# IOPower.net
KiCad netlist of a schematic drawn in Altium Designer
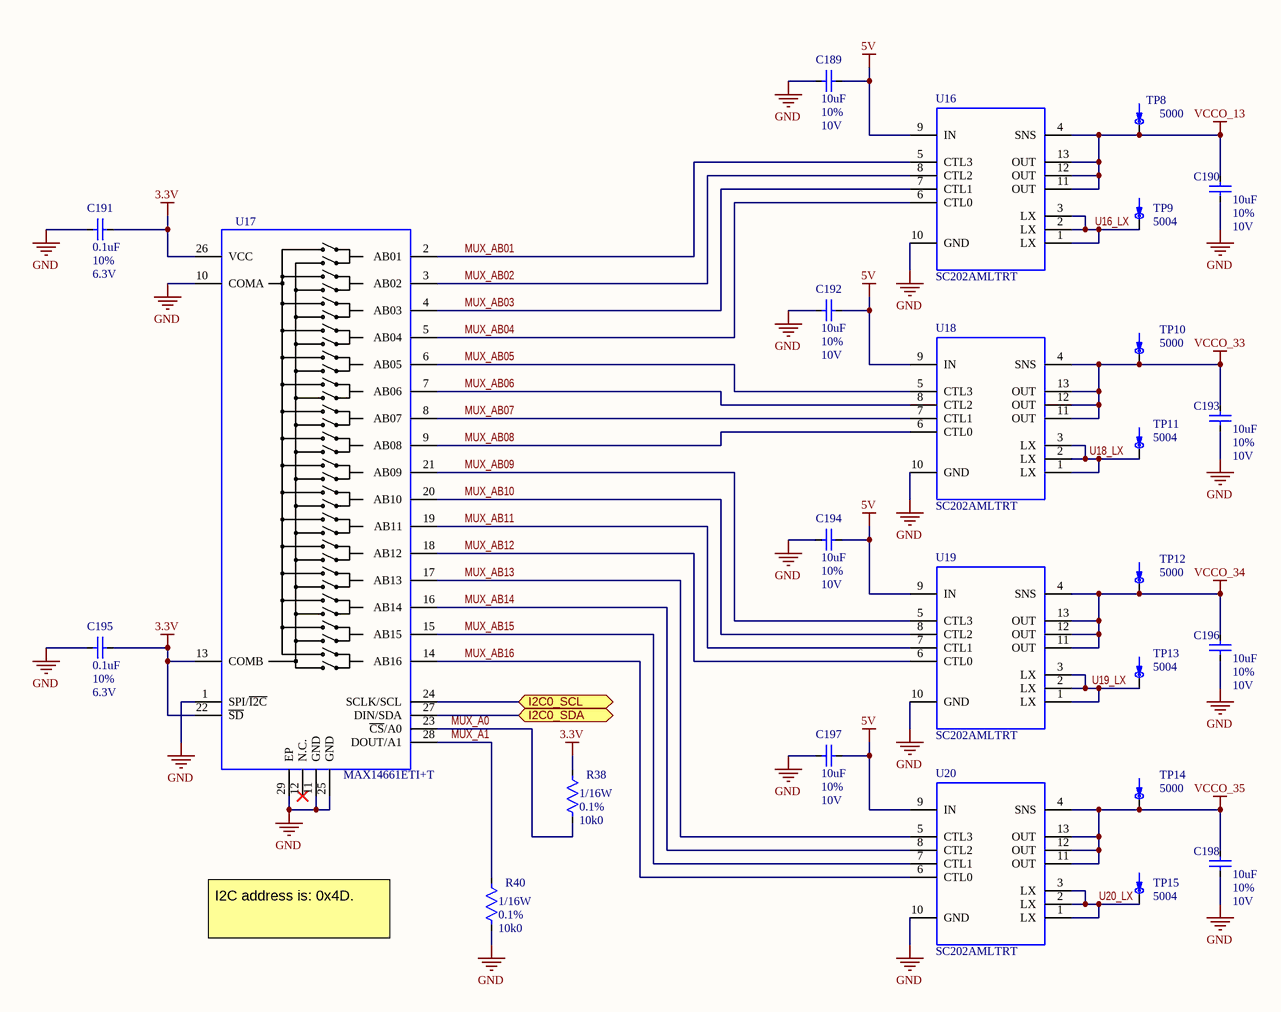
[diagram p0: IOPower.SchDoc]

(export (version "E")
  (design (tool "Eeschema 10.0.6"))
  (components
    (comp (ref "C189")
      (value "10uF")
      (footprint "CAPC1608X38N")
      (description "Capacitor ceramic, X5R, 10uF, 10V, 10%, -55 to +85 C, EIA0603")
      (fields
        (field (name "TOLERANCE") "10%")
        (field (name "VOLTAGE") "10V")
        (field (name "Comment") "CAPACITOR_NP_TYPE1")
      )
      (libsource (lib "parts") (part "CAPACITOR_NP_TYPE1"))
    )
    (comp (ref "C190")
      (value "10uF")
      (footprint "CAPC1608X38N")
      (description "Capacitor ceramic, X5R, 10uF, 10V, 10%, -55 to +85 C, EIA0603")
      (fields
        (field (name "TOLERANCE") "10%")
        (field (name "VOLTAGE") "10V")
        (field (name "Comment") "CAPACITOR_NP_TYPE1")
      )
      (libsource (lib "parts") (part "CAPACITOR_NP_TYPE1"))
    )
    (comp (ref "C191")
      (value "0.1uF")
      (footprint "CAPC0603X33N")
      (description "Capacitor ceramic, X5R, 0.1uF, 6.3V, 10%, -55 to +125 C, EIA0201")
      (fields
        (field (name "TOLERANCE") "10%")
        (field (name "VOLTAGE") "6.3V")
        (field (name "Comment") "CAPACITOR_NP_TYPE1")
      )
      (libsource (lib "parts") (part "CAPACITOR_NP_TYPE1"))
    )
    (comp (ref "C192")
      (value "10uF")
      (footprint "CAPC1608X38N")
      (description "Capacitor ceramic, X5R, 10uF, 10V, 10%, -55 to +85 C, EIA0603")
      (fields
        (field (name "TOLERANCE") "10%")
        (field (name "VOLTAGE") "10V")
        (field (name "Comment") "CAPACITOR_NP_TYPE1")
      )
      (libsource (lib "parts") (part "CAPACITOR_NP_TYPE1"))
    )
    (comp (ref "C193")
      (value "10uF")
      (footprint "CAPC1608X38N")
      (description "Capacitor ceramic, X5R, 10uF, 10V, 10%, -55 to +85 C, EIA0603")
      (fields
        (field (name "TOLERANCE") "10%")
        (field (name "VOLTAGE") "10V")
        (field (name "Comment") "CAPACITOR_NP_TYPE1")
      )
      (libsource (lib "parts") (part "CAPACITOR_NP_TYPE1"))
    )
    (comp (ref "C194")
      (value "10uF")
      (footprint "CAPC1608X38N")
      (description "Capacitor ceramic, X5R, 10uF, 10V, 10%, -55 to +85 C, EIA0603")
      (fields
        (field (name "TOLERANCE") "10%")
        (field (name "VOLTAGE") "10V")
        (field (name "Comment") "CAPACITOR_NP_TYPE1")
      )
      (libsource (lib "parts") (part "CAPACITOR_NP_TYPE1"))
    )
    (comp (ref "C195")
      (value "0.1uF")
      (footprint "CAPC0603X33N")
      (description "Capacitor ceramic, X5R, 0.1uF, 6.3V, 10%, -55 to +125 C, EIA0201")
      (fields
        (field (name "TOLERANCE") "10%")
        (field (name "VOLTAGE") "6.3V")
        (field (name "Comment") "CAPACITOR_NP_TYPE1")
      )
      (libsource (lib "parts") (part "CAPACITOR_NP_TYPE1"))
    )
    (comp (ref "C196")
      (value "10uF")
      (footprint "CAPC1608X38N")
      (description "Capacitor ceramic, X5R, 10uF, 10V, 10%, -55 to +85 C, EIA0603")
      (fields
        (field (name "TOLERANCE") "10%")
        (field (name "VOLTAGE") "10V")
        (field (name "Comment") "CAPACITOR_NP_TYPE1")
      )
      (libsource (lib "parts") (part "CAPACITOR_NP_TYPE1"))
    )
    (comp (ref "C197")
      (value "10uF")
      (footprint "CAPC1608X38N")
      (description "Capacitor ceramic, X5R, 10uF, 10V, 10%, -55 to +85 C, EIA0603")
      (fields
        (field (name "TOLERANCE") "10%")
        (field (name "VOLTAGE") "10V")
        (field (name "Comment") "CAPACITOR_NP_TYPE1")
      )
      (libsource (lib "parts") (part "CAPACITOR_NP_TYPE1"))
    )
    (comp (ref "C198")
      (value "10uF")
      (footprint "CAPC1608X38N")
      (description "Capacitor ceramic, X5R, 10uF, 10V, 10%, -55 to +85 C, EIA0603")
      (fields
        (field (name "TOLERANCE") "10%")
        (field (name "VOLTAGE") "10V")
        (field (name "Comment") "CAPACITOR_NP_TYPE1")
      )
      (libsource (lib "parts") (part "CAPACITOR_NP_TYPE1"))
    )
    (comp (ref "R38")
      (value "10k0")
      (footprint "RESC1005X33N")
      (description "Resistor, 10k0, 1/16W, 0.1%, -50 to +155 C, EIA0402")
      (fields (field (name "VOLTAGE") "50V") (field (name "POWER") "1/16W") (field (name "TOLERANCE") "0.1%"))
      (libsource (lib "parts") (part "RESISTOR_TYPE1"))
    )
    (comp (ref "R40")
      (value "10k0")
      (footprint "RESC1005X33N")
      (description "Resistor, 10k0, 1/16W, 0.1%, -50 to +155 C, EIA0402")
      (fields (field (name "VOLTAGE") "50V") (field (name "POWER") "1/16W") (field (name "TOLERANCE") "0.1%"))
      (libsource (lib "parts") (part "RESISTOR_TYPE1"))
    )
    (comp (ref "TP8")
      (value "5000")
      (footprint "KEY_5000")
      (description "Test point bead, red, Keystone Electronics, Thru-hole,")
      (fields (field (name "POWER") "Pow") (field (name "VOLTAGE") "Vol"))
      (libsource (lib "parts") (part "TEST_POINT_TYPE4"))
    )
    (comp (ref "TP9")
      (value "5004")
      (footprint "KEY_5004")
      (description "Test point bead, yellow, Keystone Electronics, Thru-hole,")
      (fields (field (name "POWER") "Pow") (field (name "VOLTAGE") "Vol"))
      (libsource (lib "parts") (part "TEST_POINT_TYPE4"))
    )
    (comp (ref "TP10")
      (value "5000")
      (footprint "KEY_5000")
      (description "Test point bead, red, Keystone Electronics, Thru-hole,")
      (fields (field (name "POWER") "Pow") (field (name "VOLTAGE") "Vol"))
      (libsource (lib "parts") (part "TEST_POINT_TYPE4"))
    )
    (comp (ref "TP11")
      (value "5004")
      (footprint "KEY_5004")
      (description "Test point bead, yellow, Keystone Electronics, Thru-hole,")
      (fields (field (name "POWER") "Pow") (field (name "VOLTAGE") "Vol"))
      (libsource (lib "parts") (part "TEST_POINT_TYPE4"))
    )
    (comp (ref "TP12")
      (value "5000")
      (footprint "KEY_5000")
      (description "Test point bead, red, Keystone Electronics, Thru-hole,")
      (fields (field (name "POWER") "Pow") (field (name "VOLTAGE") "Vol"))
      (libsource (lib "parts") (part "TEST_POINT_TYPE4"))
    )
    (comp (ref "TP13")
      (value "5004")
      (footprint "KEY_5004")
      (description "Test point bead, yellow, Keystone Electronics, Thru-hole,")
      (fields (field (name "POWER") "Pow") (field (name "VOLTAGE") "Vol"))
      (libsource (lib "parts") (part "TEST_POINT_TYPE4"))
    )
    (comp (ref "TP14")
      (value "5000")
      (footprint "KEY_5000")
      (description "Test point bead, red, Keystone Electronics, Thru-hole,")
      (fields (field (name "POWER") "Pow") (field (name "VOLTAGE") "Vol"))
      (libsource (lib "parts") (part "TEST_POINT_TYPE4"))
    )
    (comp (ref "TP15")
      (value "5004")
      (footprint "KEY_5004")
      (description "Test point bead, yellow, Keystone Electronics, Thru-hole,")
      (fields (field (name "POWER") "Pow") (field (name "VOLTAGE") "Vol"))
      (libsource (lib "parts") (part "TEST_POINT_TYPE4"))
    )
    (comp (ref "U16")
      (value "SC202AMLTRT")
      (footprint "QFN40P250X300X90-13N")
      (description "Regulator Step-down, 13-pin, 0.8V to 3.3V, 500mA, SMT, -40 to +85C, MLPQ-13")
      (fields (field (name "VOLTAGE") "0.8V to 3.3V") (field (name "MFG PART NUMBER 1") "SC202AMLTRT"))
      (libsource (lib "parts") (part "SC202AMLTRT"))
    )
    (comp (ref "U17")
      (value "MAX14661")
      (footprint "QFN40P400X400X75-29N")
      (description "Analog MUX, 16 to 2, BiCMOS")
      (fields (field (name "VOLTAGE") "+1.6V to +5.5V") (field (name "MFG PART NUMBER 1") "MAX14661ETI+T"))
      (libsource (lib "parts") (part "MAX14661"))
    )
    (comp (ref "U18")
      (value "SC202AMLTRT")
      (footprint "QFN40P250X300X90-13N")
      (description "Regulator Step-down, 13-pin, 0.8V to 3.3V, 500mA, SMT, -40 to +85C, MLPQ-13")
      (fields (field (name "VOLTAGE") "0.8V to 3.3V") (field (name "MFG PART NUMBER 1") "SC202AMLTRT"))
      (libsource (lib "parts") (part "SC202AMLTRT"))
    )
    (comp (ref "U19")
      (value "SC202AMLTRT")
      (footprint "QFN40P250X300X90-13N")
      (description "Regulator Step-down, 13-pin, 0.8V to 3.3V, 500mA, SMT, -40 to +85C, MLPQ-13")
      (fields (field (name "VOLTAGE") "0.8V to 3.3V") (field (name "MFG PART NUMBER 1") "SC202AMLTRT"))
      (libsource (lib "parts") (part "SC202AMLTRT"))
    )
    (comp (ref "U20")
      (value "SC202AMLTRT")
      (footprint "QFN40P250X300X90-13N")
      (description "Regulator Step-down, 13-pin, 0.8V to 3.3V, 500mA, SMT, -40 to +85C, MLPQ-13")
      (fields (field (name "VOLTAGE") "0.8V to 3.3V") (field (name "MFG PART NUMBER 1") "SC202AMLTRT"))
      (libsource (lib "parts") (part "SC202AMLTRT"))
    )
  )
  (nets
    (net (code "1") (name "/I2C0_SCL") (class "Default")
      (node (ref "U17") (pin "24") (pinfunction "SCLK/SCL_24") (pintype "passive"))
    )
    (net (code "2") (name "/I2C0_SDA") (class "Default")
      (node (ref "U17") (pin "27") (pinfunction "DIN/SDA_27") (pintype "passive"))
    )
    (net (code "3") (name "/MUX_A0") (class "Default")
      (node (ref "R38") (pin "2") (pinfunction "2_2") (pintype "passive"))
      (node (ref "U17") (pin "23") (pinfunction "~{CS}/A0_23") (pintype "passive"))
    )
    (net (code "4") (name "/MUX_A1") (class "Default")
      (node (ref "R40") (pin "1") (pinfunction "1_1") (pintype "passive"))
      (node (ref "U17") (pin "28") (pinfunction "DOUT/A1_28") (pintype "passive"))
    )
    (net (code "5") (name "/MUX_AB01") (class "Default")
      (node (ref "U16") (pin "5") (pinfunction "CTL3_5") (pintype "passive"))
      (node (ref "U17") (pin "2") (pinfunction "AB01_2") (pintype "passive"))
    )
    (net (code "6") (name "/MUX_AB02") (class "Default")
      (node (ref "U16") (pin "8") (pinfunction "CTL2_8") (pintype "passive"))
      (node (ref "U17") (pin "3") (pinfunction "AB02_3") (pintype "passive"))
    )
    (net (code "7") (name "/MUX_AB03") (class "Default")
      (node (ref "U16") (pin "7") (pinfunction "CTL1_7") (pintype "passive"))
      (node (ref "U17") (pin "4") (pinfunction "AB03_4") (pintype "passive"))
    )
    (net (code "8") (name "/MUX_AB04") (class "Default")
      (node (ref "U16") (pin "6") (pinfunction "CTL0_6") (pintype "passive"))
      (node (ref "U17") (pin "5") (pinfunction "AB04_5") (pintype "passive"))
    )
    (net (code "9") (name "/MUX_AB05") (class "Default")
      (node (ref "U17") (pin "6") (pinfunction "AB05_6") (pintype "passive"))
      (node (ref "U18") (pin "5") (pinfunction "CTL3_5") (pintype "passive"))
    )
    (net (code "10") (name "/MUX_AB06") (class "Default")
      (node (ref "U17") (pin "7") (pinfunction "AB06_7") (pintype "passive"))
      (node (ref "U18") (pin "8") (pinfunction "CTL2_8") (pintype "passive"))
    )
    (net (code "11") (name "/MUX_AB07") (class "Default")
      (node (ref "U17") (pin "8") (pinfunction "AB07_8") (pintype "passive"))
      (node (ref "U18") (pin "7") (pinfunction "CTL1_7") (pintype "passive"))
    )
    (net (code "12") (name "/MUX_AB08") (class "Default")
      (node (ref "U17") (pin "9") (pinfunction "AB08_9") (pintype "passive"))
      (node (ref "U18") (pin "6") (pinfunction "CTL0_6") (pintype "passive"))
    )
    (net (code "13") (name "/MUX_AB09") (class "Default")
      (node (ref "U17") (pin "21") (pinfunction "AB09_21") (pintype "passive"))
      (node (ref "U19") (pin "5") (pinfunction "CTL3_5") (pintype "passive"))
    )
    (net (code "14") (name "/MUX_AB10") (class "Default")
      (node (ref "U17") (pin "20") (pinfunction "AB10_20") (pintype "passive"))
      (node (ref "U19") (pin "8") (pinfunction "CTL2_8") (pintype "passive"))
    )
    (net (code "15") (name "/MUX_AB11") (class "Default")
      (node (ref "U17") (pin "19") (pinfunction "AB11_19") (pintype "passive"))
      (node (ref "U19") (pin "7") (pinfunction "CTL1_7") (pintype "passive"))
    )
    (net (code "16") (name "/MUX_AB12") (class "Default")
      (node (ref "U17") (pin "18") (pinfunction "AB12_18") (pintype "passive"))
      (node (ref "U19") (pin "6") (pinfunction "CTL0_6") (pintype "passive"))
    )
    (net (code "17") (name "/MUX_AB13") (class "Default")
      (node (ref "U17") (pin "17") (pinfunction "AB13_17") (pintype "passive"))
      (node (ref "U20") (pin "5") (pinfunction "CTL3_5") (pintype "passive"))
    )
    (net (code "18") (name "/MUX_AB14") (class "Default")
      (node (ref "U17") (pin "16") (pinfunction "AB14_16") (pintype "passive"))
      (node (ref "U20") (pin "8") (pinfunction "CTL2_8") (pintype "passive"))
    )
    (net (code "19") (name "/MUX_AB15") (class "Default")
      (node (ref "U17") (pin "15") (pinfunction "AB15_15") (pintype "passive"))
      (node (ref "U20") (pin "7") (pinfunction "CTL1_7") (pintype "passive"))
    )
    (net (code "20") (name "/MUX_AB16") (class "Default")
      (node (ref "U17") (pin "14") (pinfunction "AB16_14") (pintype "passive"))
      (node (ref "U20") (pin "6") (pinfunction "CTL0_6") (pintype "passive"))
    )
    (net (code "21") (name "/U16_LX") (class "Default")
      (node (ref "TP9") (pin "1") (pinfunction "1_1") (pintype "passive"))
      (node (ref "U16") (pin "1") (pinfunction "LX_1") (pintype "passive"))
      (node (ref "U16") (pin "2") (pinfunction "LX_2") (pintype "passive"))
      (node (ref "U16") (pin "3") (pinfunction "LX_3") (pintype "passive"))
    )
    (net (code "22") (name "/U18_LX") (class "Default")
      (node (ref "TP11") (pin "1") (pinfunction "1_1") (pintype "passive"))
      (node (ref "U18") (pin "1") (pinfunction "LX_1") (pintype "passive"))
      (node (ref "U18") (pin "2") (pinfunction "LX_2") (pintype "passive"))
      (node (ref "U18") (pin "3") (pinfunction "LX_3") (pintype "passive"))
    )
    (net (code "23") (name "/U19_LX") (class "Default")
      (node (ref "TP13") (pin "1") (pinfunction "1_1") (pintype "passive"))
      (node (ref "U19") (pin "1") (pinfunction "LX_1") (pintype "passive"))
      (node (ref "U19") (pin "2") (pinfunction "LX_2") (pintype "passive"))
      (node (ref "U19") (pin "3") (pinfunction "LX_3") (pintype "passive"))
    )
    (net (code "24") (name "/U20_LX") (class "Default")
      (node (ref "TP15") (pin "1") (pinfunction "1_1") (pintype "passive"))
      (node (ref "U20") (pin "1") (pinfunction "LX_1") (pintype "passive"))
      (node (ref "U20") (pin "2") (pinfunction "LX_2") (pintype "passive"))
      (node (ref "U20") (pin "3") (pinfunction "LX_3") (pintype "passive"))
    )
    (net (code "25") (name "3.3V") (class "Default")
      (node (ref "C191") (pin "1") (pinfunction "1_1") (pintype "passive"))
      (node (ref "C195") (pin "1") (pinfunction "1_1") (pintype "passive"))
      (node (ref "R38") (pin "1") (pinfunction "1_1") (pintype "passive"))
      (node (ref "U17") (pin "13") (pinfunction "COMB_13") (pintype "passive"))
      (node (ref "U17") (pin "22") (pinfunction "~{SD}_22") (pintype "passive"))
      (node (ref "U17") (pin "26") (pinfunction "VCC_26") (pintype "passive"))
    )
    (net (code "26") (name "5V") (class "Default")
      (node (ref "C189") (pin "1") (pinfunction "1_1") (pintype "passive"))
      (node (ref "C192") (pin "1") (pinfunction "1_1") (pintype "passive"))
      (node (ref "C194") (pin "1") (pinfunction "1_1") (pintype "passive"))
      (node (ref "C197") (pin "1") (pinfunction "1_1") (pintype "passive"))
      (node (ref "U16") (pin "9") (pinfunction "IN_9") (pintype "passive"))
      (node (ref "U18") (pin "9") (pinfunction "IN_9") (pintype "passive"))
      (node (ref "U19") (pin "9") (pinfunction "IN_9") (pintype "passive"))
      (node (ref "U20") (pin "9") (pinfunction "IN_9") (pintype "passive"))
    )
    (net (code "27") (name "GND") (class "Default")
      (node (ref "C189") (pin "2") (pinfunction "2_2") (pintype "passive"))
      (node (ref "C190") (pin "2") (pinfunction "2_2") (pintype "passive"))
      (node (ref "C191") (pin "2") (pinfunction "2_2") (pintype "passive"))
      (node (ref "C192") (pin "2") (pinfunction "2_2") (pintype "passive"))
      (node (ref "C193") (pin "2") (pinfunction "2_2") (pintype "passive"))
      (node (ref "C194") (pin "2") (pinfunction "2_2") (pintype "passive"))
      (node (ref "C195") (pin "2") (pinfunction "2_2") (pintype "passive"))
      (node (ref "C196") (pin "2") (pinfunction "2_2") (pintype "passive"))
      (node (ref "C197") (pin "2") (pinfunction "2_2") (pintype "passive"))
      (node (ref "C198") (pin "2") (pinfunction "2_2") (pintype "passive"))
      (node (ref "R40") (pin "2") (pinfunction "2_2") (pintype "passive"))
      (node (ref "U16") (pin "10") (pinfunction "GND_10") (pintype "passive"))
      (node (ref "U17") (pin "1") (pinfunction "SPI/~{I2C}_1") (pintype "passive"))
      (node (ref "U17") (pin "10") (pinfunction "COMA_10") (pintype "passive"))
      (node (ref "U17") (pin "11") (pinfunction "GND_11") (pintype "passive"))
      (node (ref "U17") (pin "25") (pinfunction "GND_25") (pintype "passive"))
      (node (ref "U17") (pin "29") (pinfunction "EP_29") (pintype "power_in"))
      (node (ref "U18") (pin "10") (pinfunction "GND_10") (pintype "passive"))
      (node (ref "U19") (pin "10") (pinfunction "GND_10") (pintype "passive"))
      (node (ref "U20") (pin "10") (pinfunction "GND_10") (pintype "passive"))
    )
    (net (code "28") (name "VCCO_13") (class "Default")
      (node (ref "C190") (pin "1") (pinfunction "1_1") (pintype "passive"))
      (node (ref "TP8") (pin "1") (pinfunction "1_1") (pintype "passive"))
      (node (ref "U16") (pin "11") (pinfunction "OUT_11") (pintype "passive"))
      (node (ref "U16") (pin "12") (pinfunction "OUT_12") (pintype "passive"))
      (node (ref "U16") (pin "13") (pinfunction "OUT_13") (pintype "passive"))
      (node (ref "U16") (pin "4") (pinfunction "SNS_4") (pintype "passive"))
    )
    (net (code "29") (name "VCCO_33") (class "Default")
      (node (ref "C193") (pin "1") (pinfunction "1_1") (pintype "passive"))
      (node (ref "TP10") (pin "1") (pinfunction "1_1") (pintype "passive"))
      (node (ref "U18") (pin "11") (pinfunction "OUT_11") (pintype "passive"))
      (node (ref "U18") (pin "12") (pinfunction "OUT_12") (pintype "passive"))
      (node (ref "U18") (pin "13") (pinfunction "OUT_13") (pintype "passive"))
      (node (ref "U18") (pin "4") (pinfunction "SNS_4") (pintype "passive"))
    )
    (net (code "30") (name "VCCO_34") (class "Default")
      (node (ref "C196") (pin "1") (pinfunction "1_1") (pintype "passive"))
      (node (ref "TP12") (pin "1") (pinfunction "1_1") (pintype "passive"))
      (node (ref "U19") (pin "11") (pinfunction "OUT_11") (pintype "passive"))
      (node (ref "U19") (pin "12") (pinfunction "OUT_12") (pintype "passive"))
      (node (ref "U19") (pin "13") (pinfunction "OUT_13") (pintype "passive"))
      (node (ref "U19") (pin "4") (pinfunction "SNS_4") (pintype "passive"))
    )
    (net (code "31") (name "VCCO_35") (class "Default")
      (node (ref "C198") (pin "1") (pinfunction "1_1") (pintype "passive"))
      (node (ref "TP14") (pin "1") (pinfunction "1_1") (pintype "passive"))
      (node (ref "U20") (pin "11") (pinfunction "OUT_11") (pintype "passive"))
      (node (ref "U20") (pin "12") (pinfunction "OUT_12") (pintype "passive"))
      (node (ref "U20") (pin "13") (pinfunction "OUT_13") (pintype "passive"))
      (node (ref "U20") (pin "4") (pinfunction "SNS_4") (pintype "passive"))
    )
    (net (code "32") (name "unconnected-(U17-N.C.-Pad12)") (class "Default")
      (node (ref "U17") (pin "12") (pinfunction "N.C._12") (pintype "passive+no_connect"))
    )
  )
)
